# RDA5280-Module.net
KiCad netlist of a schematic drawn in Altium Designer
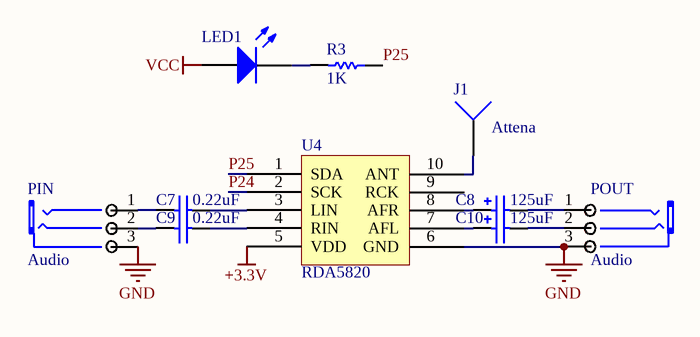
[diagram p0: RDA5280-Module.SchDoc]

(export (version "E")
  (design (tool "Eeschema 10.0.6"))
  (components
    (comp (ref "C7")
      (value "0.22uF")
      (footprint "C104")
      (description "Capacitor")
      (fields (field (name "Comment") "Cap") (field (name "PUBLISHER") "Altium Limited"))
      (libsource (lib "Miscellaneous Devices") (part "Cap"))
    )
    (comp (ref "C8")
      (value "125uF")
      (footprint "C+100，R-160")
      (description "Polarized Capacitor (Axial)")
      (fields (field (name "Comment") "Cap Pol2") (field (name "PUBLISHER") "Altium Limited"))
      (libsource (lib "Miscellaneous Devices") (part "Cap Pol2"))
    )
    (comp (ref "C9")
      (value "0.22uF")
      (footprint "C104")
      (description "Capacitor")
      (fields (field (name "Comment") "Cap") (field (name "PUBLISHER") "Altium Limited"))
      (libsource (lib "Miscellaneous Devices") (part "Cap"))
    )
    (comp (ref "C10")
      (value "125uF")
      (footprint "C+100，R-160")
      (description "Polarized Capacitor (Axial)")
      (fields (field (name "Comment") "Cap Pol2") (field (name "PUBLISHER") "Altium Limited"))
      (libsource (lib "Miscellaneous Devices") (part "Cap Pol2"))
    )
    (comp (ref "J1")
      (value "Attena")
      (footprint "PIN1")
      (description "Socket")
      (fields (field (name "PUBLISHER") "Altium Limited"))
      (libsource (lib "Miscellaneous Connectors") (part "Socket"))
    )
    (comp (ref "LED1")
      (value "LED2_red")
      (footprint "MF-1D 开发板:C+100，R-160")
      (description "Typical RED, GREEN, YELLOW, AMBER GaAs LED")
      (fields (field (name "PUBLISHER") "Altium Limited"))
      (libsource (lib "Miscellaneous Devices") (part "LED2"))
    )
    (comp (ref "PIN")
      (value "Audio")
      (footprint "PHONE_ST")
      (libsource (lib "altium-import") (part "root_0_PHONE_M_"))
    )
    (comp (ref "POUT")
      (value "Audio")
      (footprint "PHONE_ST")
      (libsource (lib "altium-import") (part "root_0_mirrored_PHONE_M_"))
    )
    (comp (ref "R3")
      (value "1K")
      (footprint "AXIAL-0.3")
      (description "Resistor")
      (fields (field (name "Comment") "Res1") (field (name "PUBLISHER") "Altium Limited"))
      (libsource (lib "Miscellaneous Devices") (part "Res1"))
    )
    (comp (ref "U4") (value "RDA5820") (footprint "RDA5820") (libsource (lib "MF-1D 开发板") (part "RDA5820")))
  )
  (nets
    (net (code "1") (name "+3.3V") (class "Default")
      (node (ref "U4") (pin "5") (pinfunction "VDD_5") (pintype "passive"))
    )
    (net (code "2") (name "/P24") (class "Default")
      (node (ref "U4") (pin "2") (pinfunction "SCK_2") (pintype "passive"))
    )
    (net (code "3") (name "/P25") (class "Default")
      (node (ref "R3") (pin "1") (pinfunction "1_1") (pintype "passive"))
      (node (ref "U4") (pin "1") (pinfunction "SDA_1") (pintype "passive"))
    )
    (net (code "4") (name "GND") (class "Default")
      (node (ref "PIN") (pin "3") (pinfunction "COM_3") (pintype "passive"))
      (node (ref "POUT") (pin "3") (pinfunction "COM_3") (pintype "passive"))
      (node (ref "U4") (pin "6") (pinfunction "GND_6") (pintype "passive"))
    )
    (net (code "5") (name "Net-(LED1-K)") (class "Default")
      (node (ref "LED1") (pin "2") (pinfunction "K_2") (pintype "passive"))
      (node (ref "R3") (pin "2") (pinfunction "2_2") (pintype "passive"))
    )
    (net (code "6") (name "Net-(PIN-CHL)") (class "Default")
      (node (ref "C7") (pin "2") (pinfunction "2_2") (pintype "passive"))
      (node (ref "PIN") (pin "1") (pinfunction "CHL_1") (pintype "passive"))
    )
    (net (code "7") (name "Net-(PIN-CHR)") (class "Default")
      (node (ref "C9") (pin "2") (pinfunction "2_2") (pintype "passive"))
      (node (ref "PIN") (pin "2") (pinfunction "CHR_2") (pintype "passive"))
    )
    (net (code "8") (name "Net-(POUT-CHL)") (class "Default")
      (node (ref "C8") (pin "2") (pinfunction "2_2") (pintype "passive"))
      (node (ref "POUT") (pin "1") (pinfunction "CHL_1") (pintype "passive"))
    )
    (net (code "9") (name "Net-(POUT-CHR)") (class "Default")
      (node (ref "C10") (pin "2") (pinfunction "2_2") (pintype "passive"))
      (node (ref "POUT") (pin "2") (pinfunction "CHR_2") (pintype "passive"))
    )
    (net (code "10") (name "Net-(U4-AFL)") (class "Default")
      (node (ref "C10") (pin "1") (pinfunction "1_1") (pintype "passive"))
      (node (ref "U4") (pin "7") (pinfunction "AFL_7") (pintype "passive"))
    )
    (net (code "11") (name "Net-(U4-AFR)") (class "Default")
      (node (ref "C8") (pin "1") (pinfunction "1_1") (pintype "passive"))
      (node (ref "U4") (pin "8") (pinfunction "AFR_8") (pintype "passive"))
    )
    (net (code "12") (name "Net-(U4-ANT)") (class "Default")
      (node (ref "J1") (pin "1") (pinfunction "1_1") (pintype "passive"))
      (node (ref "U4") (pin "10") (pinfunction "ANT_10") (pintype "passive"))
    )
    (net (code "13") (name "Net-(U4-LIN)") (class "Default")
      (node (ref "C7") (pin "1") (pinfunction "1_1") (pintype "passive"))
      (node (ref "U4") (pin "3") (pinfunction "LIN_3") (pintype "passive"))
    )
    (net (code "14") (name "Net-(U4-RIN)") (class "Default")
      (node (ref "C9") (pin "1") (pinfunction "1_1") (pintype "passive"))
      (node (ref "U4") (pin "4") (pinfunction "RIN_4") (pintype "passive"))
    )
    (net (code "15") (name "VCC") (class "Default")
      (node (ref "LED1") (pin "1") (pinfunction "A_1") (pintype "passive"))
    )
    (net (code "16") (name "unconnected-(U4-RCK-Pad9)") (class "Default")
      (node (ref "U4") (pin "9") (pinfunction "RCK_9") (pintype "passive"))
    )
  )
)
